# TransformerBoard.net
KiCad netlist of a schematic drawn in EAGLE
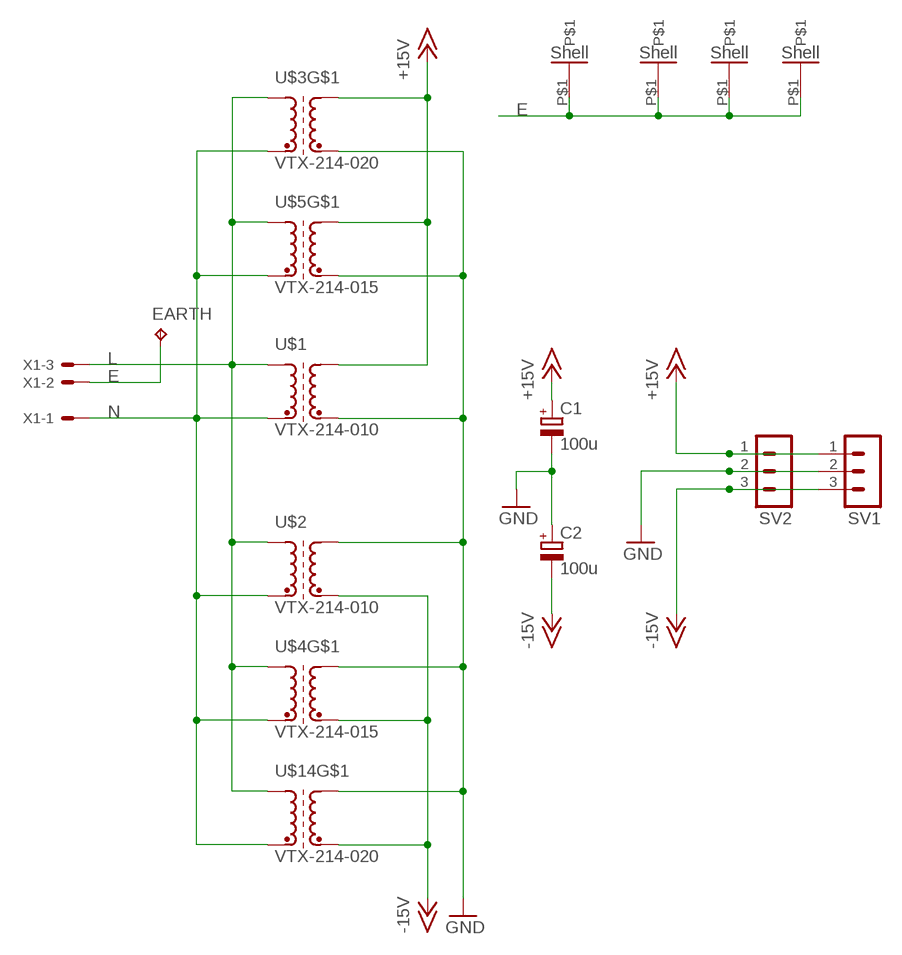
[diagram p0: schematic, sheet 1]

(export (version "E")
  (design (tool "Eeschema 10.0.6"))
  (components
    (comp (ref "C1")
      (value "100u")
      (footprint "eagle-import:E5-8,5")
      (libsource (lib "eagle-import") (part "CPOL-EUE5-8.5"))
    )
    (comp (ref "C2")
      (value "100u")
      (footprint "eagle-import:E5-8,5")
      (libsource (lib "eagle-import") (part "CPOL-EUE5-8.5"))
    )
    (comp (ref "EARTH")
      (value "TPPAD1-17")
      (footprint "eagle-import:P1-17")
      (libsource (lib "eagle-import") (part "TPPAD1-17"))
    )
    (comp (ref "SV1")
      (value "MA03-1")
      (footprint "eagle-import:MA03-1")
      (libsource (lib "eagle-import") (part "MA03-1"))
    )
    (comp (ref "SV2")
      (value "MA03-1")
      (footprint "eagle-import:MA03-1")
      (libsource (lib "eagle-import") (part "MA03-1"))
    )
    (comp (ref "U$1")
      (value "VTX-214-010")
      (footprint "eagle-import:VTX-214-010")
      (libsource (lib "eagle-import") (part "VTX-214-010"))
    )
    (comp (ref "U$2")
      (value "VTX-214-010")
      (footprint "eagle-import:VTX-214-010")
      (libsource (lib "eagle-import") (part "VTX-214-010"))
    )
    (comp (ref "U$3")
      (value "VTX-214-020")
      (footprint "eagle-import:VTX-214-020")
      (libsource (lib "eagle-import") (part "VTX-214-020"))
    )
    (comp (ref "U$4")
      (value "VTX-214-015")
      (footprint "eagle-import:VTX-214-015")
      (libsource (lib "eagle-import") (part "VTX-214-015"))
    )
    (comp (ref "U$5")
      (value "VTX-214-015")
      (footprint "eagle-import:VTX-214-015")
      (libsource (lib "eagle-import") (part "VTX-214-015"))
    )
    (comp (ref "U$14")
      (value "VTX-214-020")
      (footprint "eagle-import:VTX-214-020")
      (libsource (lib "eagle-import") (part "VTX-214-020"))
    )
    (comp (ref "X1")
      (value "KK-156-3")
      (footprint "eagle-import:KK-156-3")
      (libsource (lib "eagle-import") (part "KK-156-3"))
    )
  )
  (nets
    (net (code "1") (name "+15V") (class "Default")
      (node (ref "C1") (pin "+") (pinfunction "+_+") (pintype "passive"))
      (node (ref "SV1") (pin "1") (pinfunction "1_1") (pintype "passive"))
      (node (ref "SV2") (pin "1") (pinfunction "1_1") (pintype "passive"))
      (node (ref "U$1") (pin "P$3") (pinfunction "A2_P$3") (pintype "passive"))
      (node (ref "U$3") (pin "P$4") (pinfunction "A2_P$4") (pintype "passive"))
      (node (ref "U$5") (pin "P$4") (pinfunction "A2_P$4") (pintype "passive"))
    )
    (net (code "2") (name "-15V") (class "Default")
      (node (ref "C2") (pin "-") (pinfunction "-_-") (pintype "passive"))
      (node (ref "SV1") (pin "3") (pinfunction "3_3") (pintype "passive"))
      (node (ref "SV2") (pin "3") (pinfunction "3_3") (pintype "passive"))
      (node (ref "U$14") (pin "P$5") (pinfunction "E2_P$5") (pintype "passive"))
      (node (ref "U$2") (pin "P$4") (pinfunction "E2_P$4") (pintype "passive"))
      (node (ref "U$4") (pin "P$5") (pinfunction "E2_P$5") (pintype "passive"))
    )
    (net (code "3") (name "/E") (class "Default")
      (node (ref "EARTH") (pin "TP") (pinfunction "TP_TP") (pintype "input"))
      (node (ref "U$14") (pin "P$1") (pinfunction "P$1_P$1") (pintype "bidirectional"))
      (node (ref "U$3") (pin "P$1") (pinfunction "P$1_P$1") (pintype "bidirectional"))
      (node (ref "U$4") (pin "P$1") (pinfunction "P$1_P$1") (pintype "bidirectional"))
      (node (ref "U$5") (pin "P$1") (pinfunction "P$1_P$1") (pintype "bidirectional"))
      (node (ref "X1") (pin "2") (pinfunction "S_2") (pintype "passive"))
    )
    (net (code "4") (name "/L") (class "Default")
      (node (ref "U$1") (pin "P$1") (pinfunction "A1_P$1") (pintype "passive"))
      (node (ref "U$14") (pin "P$3") (pinfunction "A1_P$3") (pintype "passive"))
      (node (ref "U$2") (pin "P$1") (pinfunction "A1_P$1") (pintype "passive"))
      (node (ref "U$3") (pin "P$3") (pinfunction "A1_P$3") (pintype "passive"))
      (node (ref "U$4") (pin "P$3") (pinfunction "A1_P$3") (pintype "passive"))
      (node (ref "U$5") (pin "P$3") (pinfunction "A1_P$3") (pintype "passive"))
      (node (ref "X1") (pin "3") (pinfunction "S_3") (pintype "passive"))
    )
    (net (code "5") (name "/N") (class "Default")
      (node (ref "U$1") (pin "P$2") (pinfunction "E1_P$2") (pintype "passive"))
      (node (ref "U$14") (pin "P$2") (pinfunction "E1_P$2") (pintype "passive"))
      (node (ref "U$2") (pin "P$2") (pinfunction "E1_P$2") (pintype "passive"))
      (node (ref "U$3") (pin "P$2") (pinfunction "E1_P$2") (pintype "passive"))
      (node (ref "U$4") (pin "P$2") (pinfunction "E1_P$2") (pintype "passive"))
      (node (ref "U$5") (pin "P$2") (pinfunction "E1_P$2") (pintype "passive"))
      (node (ref "X1") (pin "1") (pinfunction "S_1") (pintype "passive"))
    )
    (net (code "6") (name "GND") (class "Default")
      (node (ref "C1") (pin "-") (pinfunction "-_-") (pintype "passive"))
      (node (ref "C2") (pin "+") (pinfunction "+_+") (pintype "passive"))
      (node (ref "SV1") (pin "2") (pinfunction "2_2") (pintype "passive"))
      (node (ref "SV2") (pin "2") (pinfunction "2_2") (pintype "passive"))
      (node (ref "U$1") (pin "P$4") (pinfunction "E2_P$4") (pintype "passive"))
      (node (ref "U$14") (pin "P$4") (pinfunction "A2_P$4") (pintype "passive"))
      (node (ref "U$2") (pin "P$3") (pinfunction "A2_P$3") (pintype "passive"))
      (node (ref "U$3") (pin "P$5") (pinfunction "E2_P$5") (pintype "passive"))
      (node (ref "U$4") (pin "P$4") (pinfunction "A2_P$4") (pintype "passive"))
      (node (ref "U$5") (pin "P$5") (pinfunction "E2_P$5") (pintype "passive"))
    )
  )
)
